# elevator.net
KiCad netlist of a schematic drawn in Altium Designer
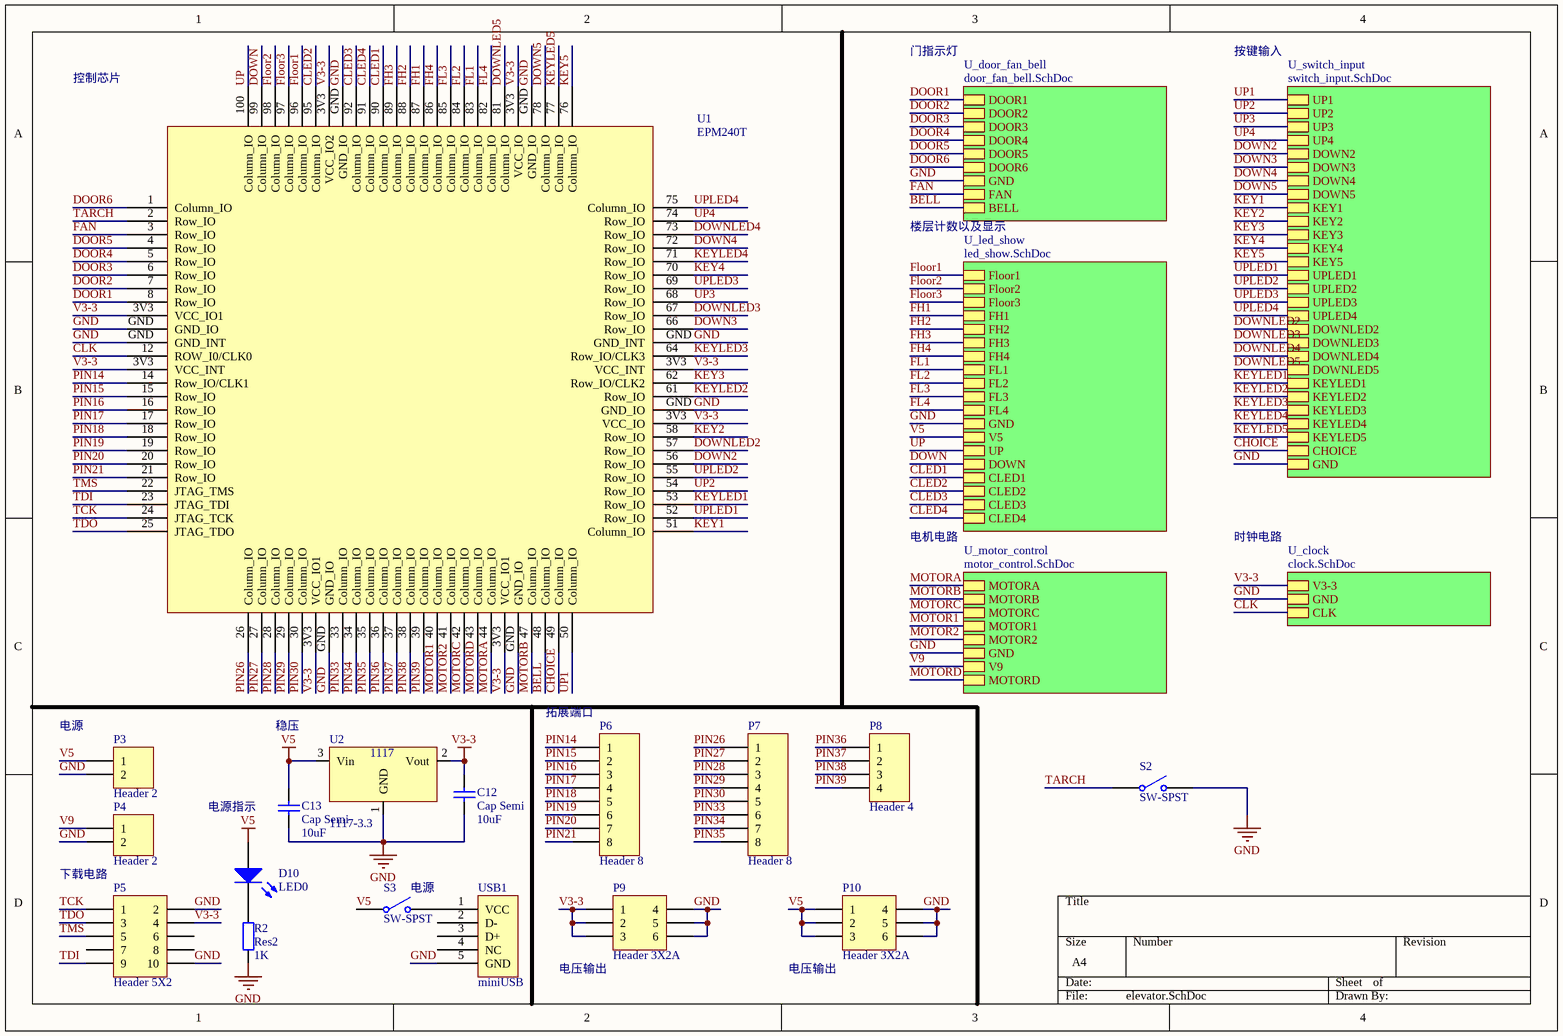
[diagram p0: elevator.SchDoc]

(export (version "E")
  (design (tool "Eeschema 10.0.6"))
  (components
    (comp (ref "C12")
      (value "Cap Semi")
      (footprint "匿名四轴飞控:0603")
      (description "Capacitor (Semiconductor SIM Model)")
      (fields (field (name "ALTIUM_VALUE") "10uF") (field (name "PUBLISHER") "Altium Limited"))
      (libsource (lib "Miscellaneous Devices") (part "Cap Semi"))
    )
    (comp (ref "C13")
      (value "Cap Semi")
      (footprint "匿名四轴飞控:0603")
      (description "Capacitor (Semiconductor SIM Model)")
      (fields (field (name "ALTIUM_VALUE") "10uF") (field (name "PUBLISHER") "Altium Limited"))
      (libsource (lib "Miscellaneous Devices") (part "Cap Semi"))
    )
    (comp (ref "D10")
      (value "LED0")
      (footprint "1206")
      (description "Typical INFRARED GaAs LED")
      (fields (field (name "PUBLISHER") "Altium Limited"))
      (libsource (lib "Miscellaneous Devices") (part "LED0"))
    )
    (comp (ref "P3")
      (value "Header 2")
      (footprint "HDR1X2")
      (description "Header, 2-Pin")
      (fields (field (name "PUBLISHER") "Altium Limited"))
      (libsource (lib "Miscellaneous Connectors") (part "Header 2"))
    )
    (comp (ref "P4")
      (value "Header 2")
      (footprint "HDR1X2")
      (description "Header, 2-Pin")
      (fields (field (name "PUBLISHER") "Altium Limited"))
      (libsource (lib "Miscellaneous Connectors") (part "Header 2"))
    )
    (comp (ref "P5")
      (value "Header 5X2")
      (footprint "P_DC3")
      (description "Header, 5-Pin, Dual row")
      (fields (field (name "PUBLISHER") "Altium Limited"))
      (libsource (lib "Miscellaneous Connectors") (part "Header 5X2"))
    )
    (comp (ref "P6")
      (value "Header 8")
      (footprint "HDR1X8")
      (description "Header, 8-Pin")
      (fields (field (name "PUBLISHER") "Altium Limited"))
      (libsource (lib "Miscellaneous Connectors") (part "Header 8"))
    )
    (comp (ref "P7")
      (value "Header 8")
      (footprint "HDR1X8")
      (description "Header, 8-Pin")
      (fields (field (name "PUBLISHER") "Altium Limited"))
      (libsource (lib "Miscellaneous Connectors") (part "Header 8"))
    )
    (comp (ref "P8")
      (value "Header 4")
      (footprint "HDR1X4")
      (description "Header, 4-Pin")
      (fields (field (name "PUBLISHER") "Altium Limited"))
      (libsource (lib "Miscellaneous Connectors") (part "Header 4"))
    )
    (comp (ref "P9")
      (value "Header 3X2A")
      (footprint "HDR2X3_CEN")
      (description "Header, 3-Pin, Dual row")
      (fields (field (name "PUBLISHER") "Altium Limited"))
      (libsource (lib "Miscellaneous Connectors") (part "Header 3X2A"))
    )
    (comp (ref "P10")
      (value "Header 3X2A")
      (footprint "HDR2X3_CEN")
      (description "Header, 3-Pin, Dual row")
      (fields (field (name "PUBLISHER") "Altium Limited"))
      (libsource (lib "Miscellaneous Connectors") (part "Header 3X2A"))
    )
    (comp (ref "R2")
      (value "Res2")
      (footprint "0603")
      (description "Resistor")
      (fields (field (name "ALTIUM_VALUE") "1K") (field (name "PUBLISHER") "Altium Limited"))
      (libsource (lib "Miscellaneous Devices") (part "Res2"))
    )
    (comp (ref "S2")
      (value "SW-SPST")
      (footprint "SW_TARCH")
      (description "Single-Pole, Single-Throw Switch")
      (fields (field (name "PUBLISHER") "Altium Limited"))
      (libsource (lib "Miscellaneous Devices") (part "SW-SPST"))
    )
    (comp (ref "S3")
      (value "SW-SPST")
      (footprint "SIP3")
      (description "Single-Pole, Single-Throw Switch")
      (fields (field (name "PUBLISHER") "Altium Limited"))
      (libsource (lib "Miscellaneous Devices") (part "SW-SPST"))
    )
    (comp (ref "U1") (value "EPM240T") (footprint "CPLD100") (libsource (lib "mylib") (part "EPM240T1005")))
    (comp (ref "U2") (value "1117-3.3") (footprint "SOT-223") (libsource (lib "MISCESCH") (part "1117B")))
    (comp (ref "USB1") (value "miniUSB") (footprint "miniUSB") (libsource (lib "mylib") (part "miniUSB")))
  )
  (nets
    (net (code "1") (name "/BELL") (class "Default")
      (node (ref "U1") (pin "48") (pinfunction "Column_IO_48") (pintype "passive"))
    )
    (net (code "2") (name "/CHOICE") (class "Default")
      (node (ref "U1") (pin "49") (pinfunction "Column_IO_49") (pintype "passive"))
    )
    (net (code "3") (name "/CLED1") (class "Default")
      (node (ref "U1") (pin "90") (pinfunction "Column_IO_90") (pintype "passive"))
    )
    (net (code "4") (name "/CLED2") (class "Default")
      (node (ref "U1") (pin "95") (pinfunction "Column_IO_95") (pintype "passive"))
    )
    (net (code "5") (name "/CLED3") (class "Default")
      (node (ref "U1") (pin "92") (pinfunction "Column_IO_92") (pintype "passive"))
    )
    (net (code "6") (name "/CLED4") (class "Default")
      (node (ref "U1") (pin "91") (pinfunction "Column_IO_91") (pintype "passive"))
    )
    (net (code "7") (name "/CLK") (class "Default")
      (node (ref "U1") (pin "12") (pinfunction "ROW_I0/CLK0_12") (pintype "passive"))
    )
    (net (code "8") (name "/DOOR1") (class "Default")
      (node (ref "U1") (pin "8") (pinfunction "Row_IO_8") (pintype "passive"))
    )
    (net (code "9") (name "/DOOR2") (class "Default")
      (node (ref "U1") (pin "7") (pinfunction "Row_IO_7") (pintype "passive"))
    )
    (net (code "10") (name "/DOOR3") (class "Default")
      (node (ref "U1") (pin "6") (pinfunction "Row_IO_6") (pintype "passive"))
    )
    (net (code "11") (name "/DOOR4") (class "Default")
      (node (ref "U1") (pin "5") (pinfunction "Row_IO_5") (pintype "passive"))
    )
    (net (code "12") (name "/DOOR5") (class "Default")
      (node (ref "U1") (pin "4") (pinfunction "Row_IO_4") (pintype "passive"))
    )
    (net (code "13") (name "/DOOR6") (class "Default")
      (node (ref "U1") (pin "1") (pinfunction "Column_IO_1") (pintype "passive"))
    )
    (net (code "14") (name "/DOWN") (class "Default")
      (node (ref "U1") (pin "99") (pinfunction "Column_IO_99") (pintype "passive"))
    )
    (net (code "15") (name "/DOWN2") (class "Default")
      (node (ref "U1") (pin "56") (pinfunction "Row_IO_56") (pintype "passive"))
    )
    (net (code "16") (name "/DOWN3") (class "Default")
      (node (ref "U1") (pin "66") (pinfunction "Row_IO_66") (pintype "passive"))
    )
    (net (code "17") (name "/DOWN4") (class "Default")
      (node (ref "U1") (pin "72") (pinfunction "Row_IO_72") (pintype "passive"))
    )
    (net (code "18") (name "/DOWN5") (class "Default")
      (node (ref "U1") (pin "78") (pinfunction "Column_IO_78") (pintype "passive"))
    )
    (net (code "19") (name "/DOWNLED2") (class "Default")
      (node (ref "U1") (pin "57") (pinfunction "Row_IO_57") (pintype "passive"))
    )
    (net (code "20") (name "/DOWNLED3") (class "Default")
      (node (ref "U1") (pin "67") (pinfunction "Row_IO_67") (pintype "passive"))
    )
    (net (code "21") (name "/DOWNLED4") (class "Default")
      (node (ref "U1") (pin "73") (pinfunction "Row_IO_73") (pintype "passive"))
    )
    (net (code "22") (name "/DOWNLED5") (class "Default")
      (node (ref "U1") (pin "81") (pinfunction "Column_IO_81") (pintype "passive"))
    )
    (net (code "23") (name "/FAN") (class "Default")
      (node (ref "U1") (pin "3") (pinfunction "Row_IO_3") (pintype "passive"))
    )
    (net (code "24") (name "/FH1") (class "Default")
      (node (ref "U1") (pin "87") (pinfunction "Column_IO_87") (pintype "passive"))
    )
    (net (code "25") (name "/FH2") (class "Default")
      (node (ref "U1") (pin "88") (pinfunction "Column_IO_88") (pintype "passive"))
    )
    (net (code "26") (name "/FH3") (class "Default")
      (node (ref "U1") (pin "89") (pinfunction "Column_IO_89") (pintype "passive"))
    )
    (net (code "27") (name "/FH4") (class "Default")
      (node (ref "U1") (pin "86") (pinfunction "Column_IO_86") (pintype "passive"))
    )
    (net (code "28") (name "/FL1") (class "Default")
      (node (ref "U1") (pin "83") (pinfunction "Column_IO_83") (pintype "passive"))
    )
    (net (code "29") (name "/FL2") (class "Default")
      (node (ref "U1") (pin "84") (pinfunction "Column_IO_84") (pintype "passive"))
    )
    (net (code "30") (name "/FL3") (class "Default")
      (node (ref "U1") (pin "85") (pinfunction "Column_IO_85") (pintype "passive"))
    )
    (net (code "31") (name "/FL4") (class "Default")
      (node (ref "U1") (pin "82") (pinfunction "Column_IO_82") (pintype "passive"))
    )
    (net (code "32") (name "/Floor1") (class "Default")
      (node (ref "U1") (pin "96") (pinfunction "Column_IO_96") (pintype "passive"))
    )
    (net (code "33") (name "/Floor2") (class "Default")
      (node (ref "U1") (pin "98") (pinfunction "Column_IO_98") (pintype "passive"))
    )
    (net (code "34") (name "/Floor3") (class "Default")
      (node (ref "U1") (pin "97") (pinfunction "Column_IO_97") (pintype "passive"))
    )
    (net (code "35") (name "/KEY1") (class "Default")
      (node (ref "U1") (pin "51") (pinfunction "Column_IO_51") (pintype "passive"))
    )
    (net (code "36") (name "/KEY2") (class "Default")
      (node (ref "U1") (pin "58") (pinfunction "Row_IO_58") (pintype "passive"))
    )
    (net (code "37") (name "/KEY3") (class "Default")
      (node (ref "U1") (pin "62") (pinfunction "Row_IO/CLK2_62") (pintype "passive"))
    )
    (net (code "38") (name "/KEY4") (class "Default")
      (node (ref "U1") (pin "70") (pinfunction "Row_IO_70") (pintype "passive"))
    )
    (net (code "39") (name "/KEY5") (class "Default")
      (node (ref "U1") (pin "76") (pinfunction "Column_IO_76") (pintype "passive"))
    )
    (net (code "40") (name "/KEYLED1") (class "Default")
      (node (ref "U1") (pin "53") (pinfunction "Row_IO_53") (pintype "passive"))
    )
    (net (code "41") (name "/KEYLED2") (class "Default")
      (node (ref "U1") (pin "61") (pinfunction "Row_IO_61") (pintype "passive"))
    )
    (net (code "42") (name "/KEYLED3") (class "Default")
      (node (ref "U1") (pin "64") (pinfunction "Row_IO/CLK3_64") (pintype "passive"))
    )
    (net (code "43") (name "/KEYLED4") (class "Default")
      (node (ref "U1") (pin "71") (pinfunction "Row_IO_71") (pintype "passive"))
    )
    (net (code "44") (name "/KEYLED5") (class "Default")
      (node (ref "U1") (pin "77") (pinfunction "Column_IO_77") (pintype "passive"))
    )
    (net (code "45") (name "/MOTOR1") (class "Default")
      (node (ref "U1") (pin "40") (pinfunction "Column_IO_40") (pintype "passive"))
    )
    (net (code "46") (name "/MOTOR2") (class "Default")
      (node (ref "U1") (pin "41") (pinfunction "Column_IO_41") (pintype "passive"))
    )
    (net (code "47") (name "/MOTORA") (class "Default")
      (node (ref "U1") (pin "44") (pinfunction "Column_IO_44") (pintype "passive"))
    )
    (net (code "48") (name "/MOTORB") (class "Default")
      (node (ref "U1") (pin "47") (pinfunction "Column_IO_47") (pintype "passive"))
    )
    (net (code "49") (name "/MOTORC") (class "Default")
      (node (ref "U1") (pin "42") (pinfunction "Column_IO_42") (pintype "passive"))
    )
    (net (code "50") (name "/MOTORD") (class "Default")
      (node (ref "U1") (pin "43") (pinfunction "Column_IO_43") (pintype "passive"))
    )
    (net (code "51") (name "/PIN14") (class "Default")
      (node (ref "P6") (pin "1") (pinfunction "1_1") (pintype "passive"))
      (node (ref "U1") (pin "14") (pinfunction "Row_IO/CLK1_14") (pintype "passive"))
    )
    (net (code "52") (name "/PIN15") (class "Default")
      (node (ref "P6") (pin "2") (pinfunction "2_2") (pintype "passive"))
      (node (ref "U1") (pin "15") (pinfunction "Row_IO_15") (pintype "passive"))
    )
    (net (code "53") (name "/PIN16") (class "Default")
      (node (ref "P6") (pin "3") (pinfunction "3_3") (pintype "passive"))
      (node (ref "U1") (pin "16") (pinfunction "Row_IO_16") (pintype "passive"))
    )
    (net (code "54") (name "/PIN17") (class "Default")
      (node (ref "P6") (pin "4") (pinfunction "4_4") (pintype "passive"))
      (node (ref "U1") (pin "17") (pinfunction "Row_IO_17") (pintype "passive"))
    )
    (net (code "55") (name "/PIN18") (class "Default")
      (node (ref "P6") (pin "5") (pinfunction "5_5") (pintype "passive"))
      (node (ref "U1") (pin "18") (pinfunction "Row_IO_18") (pintype "passive"))
    )
    (net (code "56") (name "/PIN19") (class "Default")
      (node (ref "P6") (pin "6") (pinfunction "6_6") (pintype "passive"))
      (node (ref "U1") (pin "19") (pinfunction "Row_IO_19") (pintype "passive"))
    )
    (net (code "57") (name "/PIN20") (class "Default")
      (node (ref "P6") (pin "7") (pinfunction "7_7") (pintype "passive"))
      (node (ref "U1") (pin "20") (pinfunction "Row_IO_20") (pintype "passive"))
    )
    (net (code "58") (name "/PIN21") (class "Default")
      (node (ref "P6") (pin "8") (pinfunction "8_8") (pintype "passive"))
      (node (ref "U1") (pin "21") (pinfunction "Row_IO_21") (pintype "passive"))
    )
    (net (code "59") (name "/PIN26") (class "Default")
      (node (ref "P7") (pin "1") (pinfunction "1_1") (pintype "passive"))
      (node (ref "U1") (pin "26") (pinfunction "Column_IO_26") (pintype "passive"))
    )
    (net (code "60") (name "/PIN27") (class "Default")
      (node (ref "P7") (pin "2") (pinfunction "2_2") (pintype "passive"))
      (node (ref "U1") (pin "27") (pinfunction "Column_IO_27") (pintype "passive"))
    )
    (net (code "61") (name "/PIN28") (class "Default")
      (node (ref "P7") (pin "3") (pinfunction "3_3") (pintype "passive"))
      (node (ref "U1") (pin "28") (pinfunction "Column_IO_28") (pintype "passive"))
    )
    (net (code "62") (name "/PIN29") (class "Default")
      (node (ref "P7") (pin "4") (pinfunction "4_4") (pintype "passive"))
      (node (ref "U1") (pin "29") (pinfunction "Column_IO_29") (pintype "passive"))
    )
    (net (code "63") (name "/PIN30") (class "Default")
      (node (ref "P7") (pin "5") (pinfunction "5_5") (pintype "passive"))
      (node (ref "U1") (pin "30") (pinfunction "Column_IO_30") (pintype "passive"))
    )
    (net (code "64") (name "/PIN33") (class "Default")
      (node (ref "P7") (pin "6") (pinfunction "6_6") (pintype "passive"))
      (node (ref "U1") (pin "33") (pinfunction "Column_IO_33") (pintype "passive"))
    )
    (net (code "65") (name "/PIN34") (class "Default")
      (node (ref "P7") (pin "7") (pinfunction "7_7") (pintype "passive"))
      (node (ref "U1") (pin "34") (pinfunction "Column_IO_34") (pintype "passive"))
    )
    (net (code "66") (name "/PIN35") (class "Default")
      (node (ref "P7") (pin "8") (pinfunction "8_8") (pintype "passive"))
      (node (ref "U1") (pin "35") (pinfunction "Column_IO_35") (pintype "passive"))
    )
    (net (code "67") (name "/PIN36") (class "Default")
      (node (ref "P8") (pin "1") (pinfunction "1_1") (pintype "passive"))
      (node (ref "U1") (pin "36") (pinfunction "Column_IO_36") (pintype "passive"))
    )
    (net (code "68") (name "/PIN37") (class "Default")
      (node (ref "P8") (pin "2") (pinfunction "2_2") (pintype "passive"))
      (node (ref "U1") (pin "37") (pinfunction "Column_IO_37") (pintype "passive"))
    )
    (net (code "69") (name "/PIN38") (class "Default")
      (node (ref "P8") (pin "3") (pinfunction "3_3") (pintype "passive"))
      (node (ref "U1") (pin "38") (pinfunction "Column_IO_38") (pintype "passive"))
    )
    (net (code "70") (name "/PIN39") (class "Default")
      (node (ref "P8") (pin "4") (pinfunction "4_4") (pintype "passive"))
      (node (ref "U1") (pin "39") (pinfunction "Column_IO_39") (pintype "passive"))
    )
    (net (code "71") (name "/TARCH") (class "Default")
      (node (ref "S2") (pin "1") (pinfunction "COMMON_1") (pintype "passive"))
      (node (ref "U1") (pin "2") (pinfunction "Row_IO_2") (pintype "passive"))
    )
    (net (code "72") (name "/TCK") (class "Default")
      (node (ref "P5") (pin "1") (pinfunction "1_1") (pintype "passive"))
      (node (ref "U1") (pin "24") (pinfunction "JTAG_TCK_24") (pintype "passive"))
    )
    (net (code "73") (name "/TDI") (class "Default")
      (node (ref "P5") (pin "9") (pinfunction "9_9") (pintype "passive"))
      (node (ref "U1") (pin "23") (pinfunction "JTAG_TDI_23") (pintype "passive"))
    )
    (net (code "74") (name "/TDO") (class "Default")
      (node (ref "P5") (pin "3") (pinfunction "3_3") (pintype "passive"))
      (node (ref "U1") (pin "25") (pinfunction "JTAG_TDO_25") (pintype "passive"))
    )
    (net (code "75") (name "/TMS") (class "Default")
      (node (ref "P5") (pin "5") (pinfunction "5_5") (pintype "passive"))
      (node (ref "U1") (pin "22") (pinfunction "JTAG_TMS_22") (pintype "passive"))
    )
    (net (code "76") (name "/UP") (class "Default")
      (node (ref "U1") (pin "100") (pinfunction "Column_IO_100") (pintype "passive"))
    )
    (net (code "77") (name "/UP1") (class "Default")
      (node (ref "U1") (pin "50") (pinfunction "Column_IO_50") (pintype "passive"))
    )
    (net (code "78") (name "/UP2") (class "Default")
      (node (ref "U1") (pin "54") (pinfunction "Row_IO_54") (pintype "passive"))
    )
    (net (code "79") (name "/UP3") (class "Default")
      (node (ref "U1") (pin "68") (pinfunction "Row_IO_68") (pintype "passive"))
    )
    (net (code "80") (name "/UP4") (class "Default")
      (node (ref "U1") (pin "74") (pinfunction "Row_IO_74") (pintype "passive"))
    )
    (net (code "81") (name "/UPLED1") (class "Default")
      (node (ref "U1") (pin "52") (pinfunction "Row_IO_52") (pintype "passive"))
    )
    (net (code "82") (name "/UPLED2") (class "Default")
      (node (ref "U1") (pin "55") (pinfunction "Row_IO_55") (pintype "passive"))
    )
    (net (code "83") (name "/UPLED3") (class "Default")
      (node (ref "U1") (pin "69") (pinfunction "Row_IO_69") (pintype "passive"))
    )
    (net (code "84") (name "/UPLED4") (class "Default")
      (node (ref "U1") (pin "75") (pinfunction "Column_IO_75") (pintype "passive"))
    )
    (net (code "85") (name "/V9") (class "Default")
      (node (ref "P4") (pin "1") (pinfunction "1_1") (pintype "passive"))
    )
    (net (code "86") (name "GND") (class "Default")
      (node (ref "C12") (pin "2") (pinfunction "2_2") (pintype "passive"))
      (node (ref "C13") (pin "2") (pinfunction "2_2") (pintype "passive"))
      (node (ref "P10") (pin "4") (pinfunction "4_4") (pintype "passive"))
      (node (ref "P10") (pin "5") (pinfunction "5_5") (pintype "passive"))
      (node (ref "P10") (pin "6") (pinfunction "6_6") (pintype "passive"))
      (node (ref "P3") (pin "2") (pinfunction "2_2") (pintype "passive"))
      (node (ref "P4") (pin "2") (pinfunction "2_2") (pintype "passive"))
      (node (ref "P5") (pin "10") (pinfunction "10_10") (pintype "passive"))
      (node (ref "P5") (pin "2") (pinfunction "2_2") (pintype "passive"))
      (node (ref "P9") (pin "4") (pinfunction "4_4") (pintype "passive"))
      (node (ref "P9") (pin "5") (pinfunction "5_5") (pintype "passive"))
      (node (ref "P9") (pin "6") (pinfunction "6_6") (pintype "passive"))
      (node (ref "R2") (pin "1") (pinfunction "1_1") (pintype "passive"))
      (node (ref "S2") (pin "2") (pinfunction "NO_2") (pintype "passive"))
      (node (ref "U1") (pin "GND") (pinfunction "GND_IO_GND") (pintype "passive"))
      (node (ref "U2") (pin "1") (pinfunction "GND_1") (pintype "passive"))
      (node (ref "USB1") (pin "5") (pinfunction "GND_5") (pintype "passive"))
    )
    (net (code "87") (name "Net-(D10-K)") (class "Default")
      (node (ref "D10") (pin "2") (pinfunction "K_2") (pintype "passive"))
      (node (ref "R2") (pin "2") (pinfunction "2_2") (pintype "passive"))
    )
    (net (code "88") (name "Net-(S3-NO)") (class "Default")
      (node (ref "S3") (pin "2") (pinfunction "NO_2") (pintype "passive"))
      (node (ref "USB1") (pin "1") (pinfunction "VCC_1") (pintype "passive"))
    )
    (net (code "89") (name "V3-3") (class "Default")
      (node (ref "C12") (pin "1") (pinfunction "1_1") (pintype "passive"))
      (node (ref "P5") (pin "4") (pinfunction "4_4") (pintype "passive"))
      (node (ref "P9") (pin "1") (pinfunction "1_1") (pintype "passive"))
      (node (ref "P9") (pin "2") (pinfunction "2_2") (pintype "passive"))
      (node (ref "P9") (pin "3") (pinfunction "3_3") (pintype "passive"))
      (node (ref "U1") (pin "3V3") (pinfunction "VCC_IO1_3V3") (pintype "passive"))
      (node (ref "U2") (pin "2") (pinfunction "Vout_2") (pintype "passive"))
    )
    (net (code "90") (name "V5") (class "Default")
      (node (ref "C13") (pin "1") (pinfunction "1_1") (pintype "passive"))
      (node (ref "D10") (pin "1") (pinfunction "A_1") (pintype "passive"))
      (node (ref "P10") (pin "1") (pinfunction "1_1") (pintype "passive"))
      (node (ref "P10") (pin "2") (pinfunction "2_2") (pintype "passive"))
      (node (ref "P10") (pin "3") (pinfunction "3_3") (pintype "passive"))
      (node (ref "P3") (pin "1") (pinfunction "1_1") (pintype "passive"))
      (node (ref "S3") (pin "1") (pinfunction "COMMON_1") (pintype "passive"))
      (node (ref "U2") (pin "3") (pinfunction "Vin_3") (pintype "passive"))
    )
    (net (code "91") (name "unconnected-(P5-Pad6)") (class "Default")
      (node (ref "P5") (pin "6") (pinfunction "6_6") (pintype "passive"))
    )
    (net (code "92") (name "unconnected-(P5-Pad7)") (class "Default")
      (node (ref "P5") (pin "7") (pinfunction "7_7") (pintype "passive"))
    )
    (net (code "93") (name "unconnected-(P5-Pad8)") (class "Default")
      (node (ref "P5") (pin "8") (pinfunction "8_8") (pintype "passive"))
    )
    (net (code "94") (name "unconnected-(USB1-D+-Pad3)") (class "Default")
      (node (ref "USB1") (pin "3") (pinfunction "D+_3") (pintype "passive"))
    )
    (net (code "95") (name "unconnected-(USB1-D--Pad2)") (class "Default")
      (node (ref "USB1") (pin "2") (pinfunction "D-_2") (pintype "passive"))
    )
    (net (code "96") (name "unconnected-(USB1-NC-Pad4)") (class "Default")
      (node (ref "USB1") (pin "4") (pinfunction "NC_4") (pintype "passive"))
    )
  )
)
